# current_monitor_v1-1.net
KiCad netlist of a schematic drawn in EAGLE
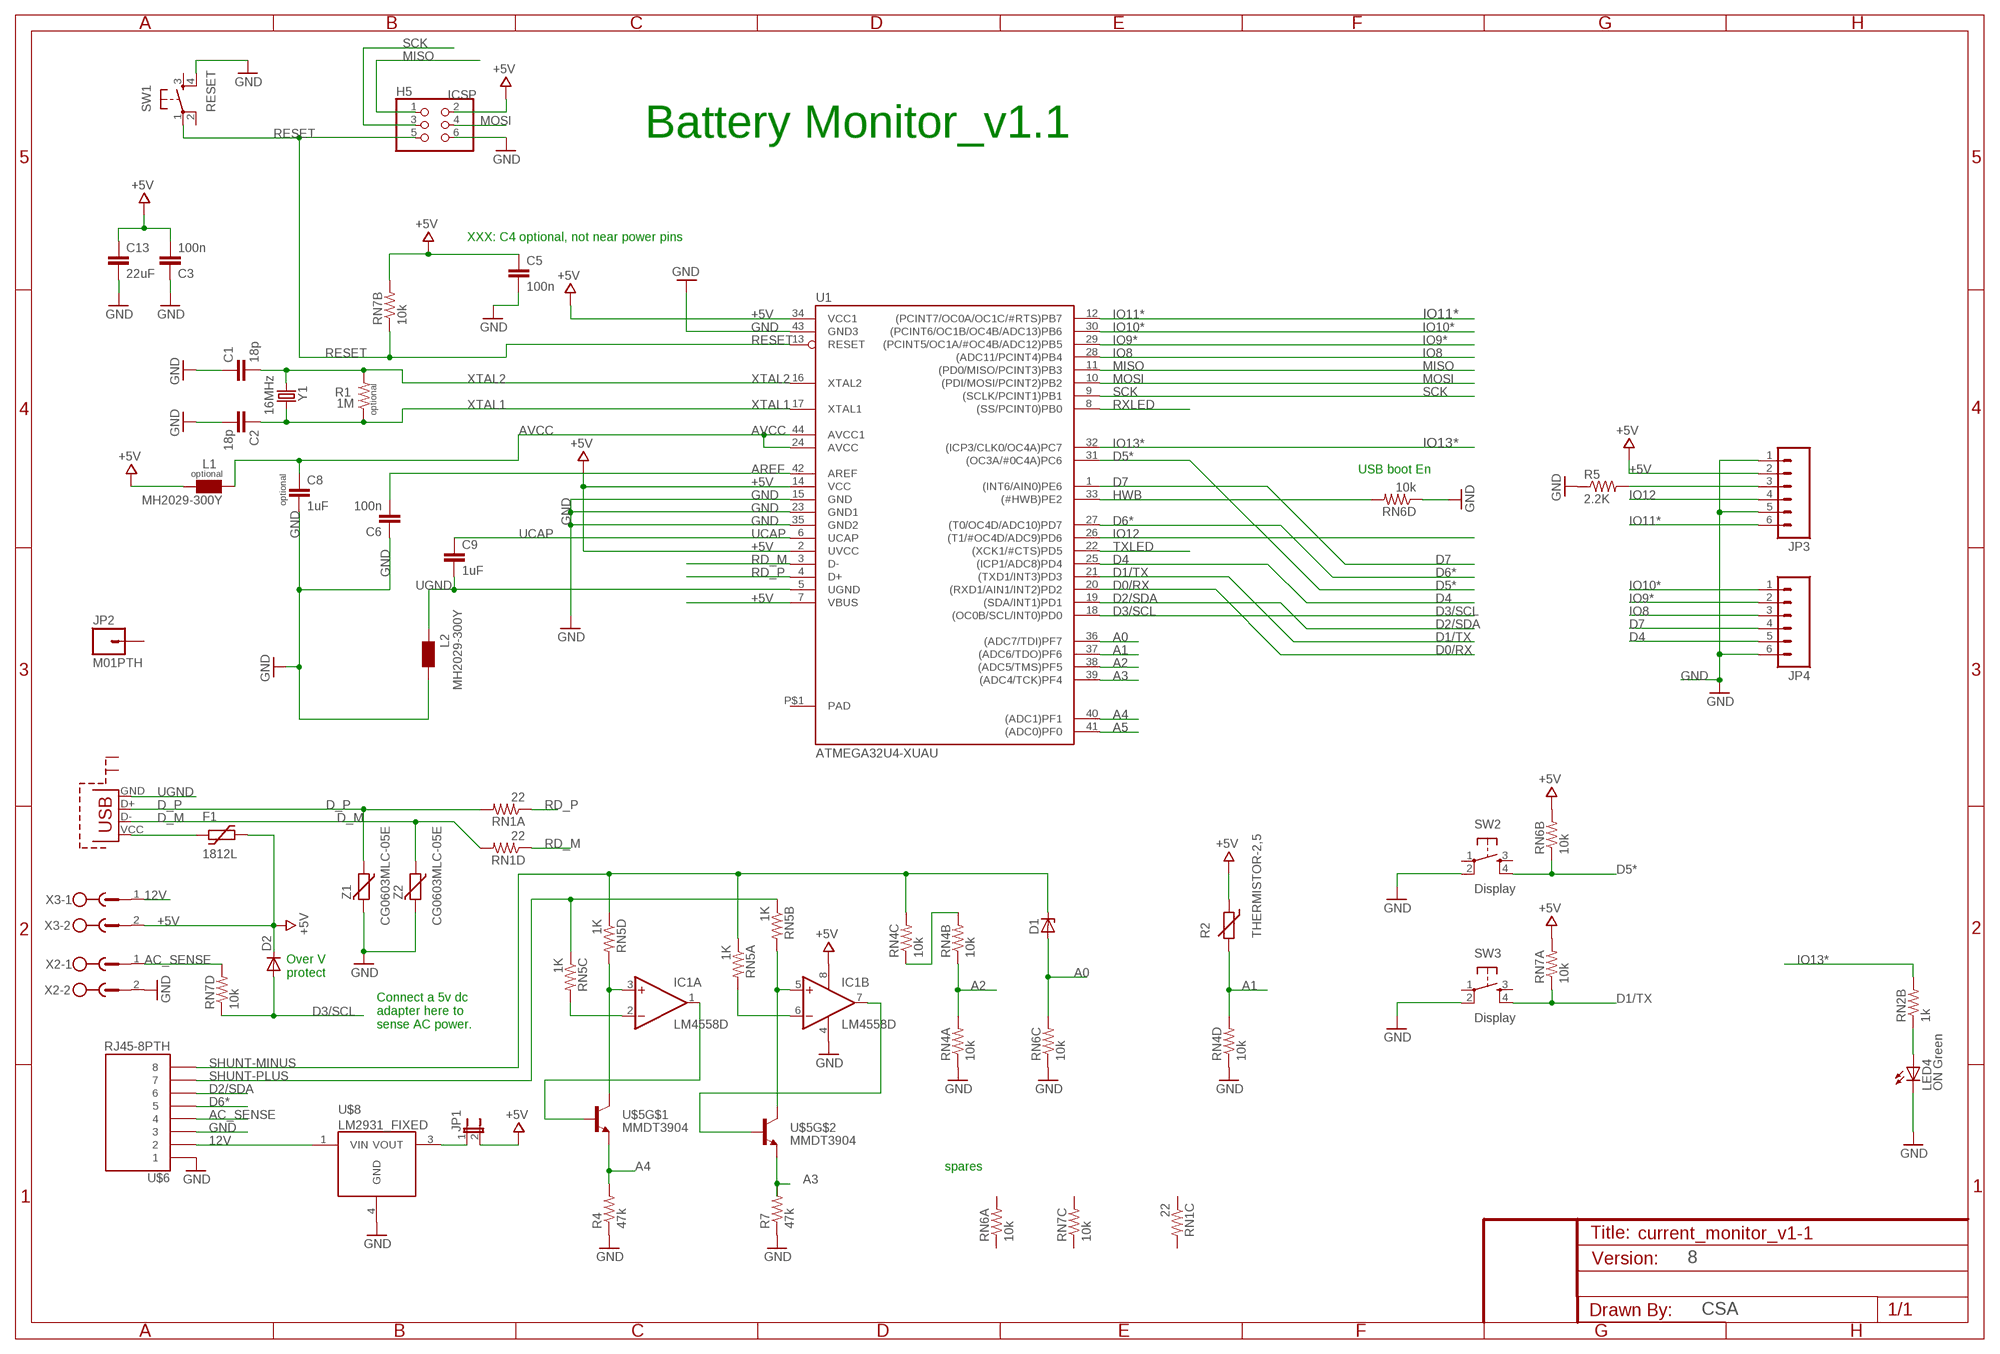
[diagram p0: schematic, sheet 1]

(export (version "E")
  (design (tool "Eeschema 10.0.6"))
  (components
    (comp (ref "C1")
      (value "18p")
      (footprint "eagle-import:0805")
      (libsource (lib "eagle-import") (part "CAP0805"))
    )
    (comp (ref "C2")
      (value "18p")
      (footprint "eagle-import:0805")
      (libsource (lib "eagle-import") (part "CAP0805"))
    )
    (comp (ref "C3")
      (value "100n")
      (footprint "eagle-import:0805")
      (libsource (lib "eagle-import") (part "CAP0805"))
    )
    (comp (ref "C5")
      (value "100n")
      (footprint "eagle-import:0805")
      (libsource (lib "eagle-import") (part "CAP0805"))
    )
    (comp (ref "C6")
      (value "100n")
      (footprint "eagle-import:0805")
      (libsource (lib "eagle-import") (part "CAP0805"))
    )
    (comp (ref "C8")
      (value "1uF")
      (footprint "eagle-import:0805")
      (libsource (lib "eagle-import") (part "CAP0805"))
    )
    (comp (ref "C9")
      (value "1uF")
      (footprint "eagle-import:0805")
      (libsource (lib "eagle-import") (part "CAP0805"))
    )
    (comp (ref "C13")
      (value "22uF")
      (footprint "eagle-import:1206")
      (libsource (lib "eagle-import") (part "CAP1206"))
    )
    (comp (ref "D1")
      (value "ZENER-DIODEZD-5")
      (footprint "eagle-import:ZDIO-5")
      (libsource (lib "eagle-import") (part "ZENER-DIODEZD-5"))
    )
    (comp (ref "D2")
      (value "DIODESMA")
      (footprint "eagle-import:SMA-DIODE")
      (libsource (lib "eagle-import") (part "DIODESMA"))
    )
    (comp (ref "F1")
      (value "1812L")
      (footprint "eagle-import:1812L")
      (libsource (lib "eagle-import") (part "1812L"))
    )
    (comp (ref "H5")
      (value "ICSP")
      (footprint "eagle-import:2X03")
      (libsource (lib "eagle-import") (part "PINHD-2X3"))
    )
    (comp (ref "IC1")
      (value "LM4558D")
      (footprint "eagle-import:SO08")
      (libsource (lib "eagle-import") (part "4558DLM"))
    )
    (comp (ref "JP1")
      (value "JUMPER-2-OLDPTH_LOCK")
      (footprint "eagle-import:1X02_LOCK")
      (libsource (lib "eagle-import") (part "JUMPER-2-OLDPTH_LOCK"))
    )
    (comp (ref "JP2")
      (value "M01PTH")
      (footprint "eagle-import:1X01")
      (libsource (lib "eagle-import") (part "M01PTH"))
    )
    (comp (ref "JP3")
      (value "M06FEMALE_LOCK")
      (footprint "eagle-import:1X06_FEMALE_LOCK.010")
      (libsource (lib "eagle-import") (part "M06FEMALE_LOCK"))
    )
    (comp (ref "JP4")
      (value "M06FEMALE_LOCK")
      (footprint "eagle-import:1X06_FEMALE_LOCK.010")
      (libsource (lib "eagle-import") (part "M06FEMALE_LOCK"))
    )
    (comp (ref "L1")
      (value "MH2029-300Y")
      (footprint "eagle-import:0805")
      (libsource (lib "eagle-import") (part "WE-CBF_0805"))
    )
    (comp (ref "L2")
      (value "MH2029-300Y")
      (footprint "eagle-import:0805")
      (libsource (lib "eagle-import") (part "WE-CBF_0805"))
    )
    (comp (ref "LED4")
      (value "ON Green")
      (footprint "eagle-import:LED0805")
      (libsource (lib "eagle-import") (part "LED0805"))
    )
    (comp (ref "R1")
      (value "1M")
      (footprint "eagle-import:0805")
      (libsource (lib "eagle-import") (part "RESISTOR0805-RES"))
    )
    (comp (ref "R2")
      (value "THERMISTOR-2,5")
      (footprint "eagle-import:RS-2,5")
      (libsource (lib "eagle-import") (part "THERMISTOR-2,5"))
    )
    (comp (ref "R4")
      (value "47k")
      (footprint "eagle-import:0805")
      (libsource (lib "eagle-import") (part "RESISTOR0805-RES"))
    )
    (comp (ref "R5")
      (value "2.2K")
      (footprint "eagle-import:0805")
      (libsource (lib "eagle-import") (part "RESISTOR0805-RES"))
    )
    (comp (ref "R7")
      (value "47k")
      (footprint "eagle-import:0805")
      (libsource (lib "eagle-import") (part "RESISTOR0805-RES"))
    )
    (comp (ref "RN1")
      (value "22")
      (footprint "eagle-import:CRA06S")
      (libsource (lib "eagle-import") (part "RESISTOR-ARRAYCRA06S"))
    )
    (comp (ref "RN2")
      (value "1k")
      (footprint "eagle-import:CRA06S")
      (libsource (lib "eagle-import") (part "RESISTOR-ARRAYCRA06S"))
    )
    (comp (ref "RN4")
      (value "10k")
      (footprint "eagle-import:CRA06S")
      (libsource (lib "eagle-import") (part "RESISTOR-ARRAYCRA06S"))
    )
    (comp (ref "RN5")
      (value "1K")
      (footprint "eagle-import:CRA06S")
      (libsource (lib "eagle-import") (part "RESISTOR-ARRAYCRA06S"))
    )
    (comp (ref "RN6")
      (value "10k")
      (footprint "eagle-import:CRA06S")
      (libsource (lib "eagle-import") (part "RESISTOR-ARRAYCRA06S"))
    )
    (comp (ref "RN7")
      (value "10k")
      (footprint "eagle-import:CRA06S")
      (libsource (lib "eagle-import") (part "RESISTOR-ARRAYCRA06S"))
    )
    (comp (ref "SW1")
      (value "RESET")
      (footprint "eagle-import:TACTILE-PTH")
      (libsource (lib "eagle-import") (part "TAC_SWITCHPTH"))
    )
    (comp (ref "SW2")
      (value "Display")
      (footprint "eagle-import:TACTILE-PTH")
      (libsource (lib "eagle-import") (part "TAC_SWITCHPTH"))
    )
    (comp (ref "SW3")
      (value "Display")
      (footprint "eagle-import:TACTILE-PTH")
      (libsource (lib "eagle-import") (part "TAC_SWITCHPTH"))
    )
    (comp (ref "U$5")
      (value "MMDT3904")
      (footprint "eagle-import:SOT363")
      (libsource (lib "eagle-import") (part "MMDT3904"))
    )
    (comp (ref "U$6")
      (value "RJ45-8PTH")
      (footprint "eagle-import:RJ45-8")
      (libsource (lib "eagle-import") (part "RJ45-8PTH"))
    )
    (comp (ref "U$8")
      (value "LM2931_FIXED")
      (footprint "eagle-import:DPAK")
      (libsource (lib "eagle-import") (part "LM2931_FIXED"))
    )
    (comp (ref "U$12")
      (value "USB-MICRO-B-UNIVERSAL")
      (footprint "eagle-import:USB-MICRO-B-UNIVERSAL")
      (libsource (lib "eagle-import") (part "USB-MICRO-B-UNIVERSAL"))
    )
    (comp (ref "U1")
      (value "ATMEGA32U4-XUAU")
      (footprint "eagle-import:TQFP44-PAD")
      (libsource (lib "eagle-import") (part "ATMEGA32U4-XUAU"))
    )
    (comp (ref "X2")
      (value "MSTBV2")
      (footprint "eagle-import:MSTBV2")
      (libsource (lib "eagle-import") (part "MSTBV2"))
    )
    (comp (ref "X3")
      (value "MSTBV2")
      (footprint "eagle-import:MSTBV2")
      (libsource (lib "eagle-import") (part "MSTBV2"))
    )
    (comp (ref "Y1")
      (value "16MHz")
      (footprint "eagle-import:HC49US")
      (libsource (lib "eagle-import") (part "CRYSTALHC49US"))
    )
    (comp (ref "Z1")
      (value "CG0603MLC-05E")
      (footprint "eagle-import:CT_CN0603")
      (libsource (lib "eagle-import") (part "VARISTORCN0603"))
    )
    (comp (ref "Z2")
      (value "CG0603MLC-05E")
      (footprint "eagle-import:CT_CN0603")
      (libsource (lib "eagle-import") (part "VARISTORCN0603"))
    )
  )
  (nets
    (net (code "1") (name "+5V") (class "Default")
      (node (ref "C13") (pin "1") (pinfunction "1_1") (pintype "passive"))
      (node (ref "C3") (pin "2") (pinfunction "2_2") (pintype "passive"))
      (node (ref "C5") (pin "1") (pinfunction "1_1") (pintype "passive"))
      (node (ref "D2") (pin "C") (pinfunction "C_C") (pintype "passive"))
      (node (ref "F1") (pin "P$2") (pinfunction "2_P$2") (pintype "passive"))
      (node (ref "H5") (pin "2") (pinfunction "2_2") (pintype "passive"))
      (node (ref "IC1") (pin "8") (pinfunction "V+_8") (pintype "power_in"))
      (node (ref "JP1") (pin "2") (pinfunction "2_2") (pintype "passive"))
      (node (ref "JP3") (pin "2") (pinfunction "2_2") (pintype "passive"))
      (node (ref "L1") (pin "1") (pinfunction "1_1") (pintype "passive"))
      (node (ref "R2") (pin "1") (pinfunction "1_1") (pintype "passive"))
      (node (ref "RN6") (pin "7") (pinfunction "2_7") (pintype "passive"))
      (node (ref "RN7") (pin "7") (pinfunction "2_7") (pintype "passive"))
      (node (ref "RN7") (pin "8") (pinfunction "2_8") (pintype "passive"))
      (node (ref "U1") (pin "14") (pinfunction "VCC_14") (pintype "power_in"))
      (node (ref "U1") (pin "2") (pinfunction "UVCC_2") (pintype "power_in"))
      (node (ref "U1") (pin "34") (pinfunction "VCC1_34") (pintype "power_in"))
      (node (ref "U1") (pin "7") (pinfunction "VBUS_7") (pintype "input"))
      (node (ref "X3") (pin "2") (pinfunction "SK_2") (pintype "passive"))
    )
    (net (code "2") (name "/12V") (class "Default")
      (node (ref "U$6") (pin "2") (pinfunction "2_2") (pintype "bidirectional"))
      (node (ref "U$8") (pin "1") (pinfunction "VIN_1") (pintype "bidirectional"))
      (node (ref "X3") (pin "1") (pinfunction "SK_1") (pintype "passive"))
    )
    (net (code "3") (name "/A0") (class "Default")
      (node (ref "D1") (pin "A") (pinfunction "A_A") (pintype "passive"))
      (node (ref "RN6") (pin "6") (pinfunction "2_6") (pintype "passive"))
      (node (ref "U1") (pin "36") (pinfunction "(ADC7/TDI)PF7_36") (pintype "bidirectional"))
    )
    (net (code "4") (name "/A1") (class "Default")
      (node (ref "R2") (pin "2") (pinfunction "2_2") (pintype "passive"))
      (node (ref "RN4") (pin "5") (pinfunction "2_5") (pintype "passive"))
      (node (ref "U1") (pin "37") (pinfunction "(ADC6/TDO)PF6_37") (pintype "bidirectional"))
    )
    (net (code "5") (name "/A2") (class "Default")
      (node (ref "RN4") (pin "2") (pinfunction "1_2") (pintype "passive"))
      (node (ref "RN4") (pin "8") (pinfunction "2_8") (pintype "passive"))
      (node (ref "U1") (pin "38") (pinfunction "(ADC5/TMS)PF5_38") (pintype "bidirectional"))
    )
    (net (code "6") (name "/A3") (class "Default")
      (node (ref "R7") (pin "2") (pinfunction "2_2") (pintype "passive"))
      (node (ref "U$5") (pin "1") (pinfunction "E_1") (pintype "passive"))
      (node (ref "U1") (pin "39") (pinfunction "(ADC4/TCK)PF4_39") (pintype "bidirectional"))
    )
    (net (code "7") (name "/A4") (class "Default")
      (node (ref "R4") (pin "2") (pinfunction "2_2") (pintype "passive"))
      (node (ref "U$5") (pin "4") (pinfunction "E_4") (pintype "passive"))
      (node (ref "U1") (pin "40") (pinfunction "(ADC1)PF1_40") (pintype "bidirectional"))
    )
    (net (code "8") (name "/A5") (class "Default")
      (node (ref "U1") (pin "41") (pinfunction "(ADC0)PF0_41") (pintype "bidirectional"))
    )
    (net (code "9") (name "/AC_SENSE") (class "Default")
      (node (ref "RN7") (pin "5") (pinfunction "2_5") (pintype "passive"))
      (node (ref "U$6") (pin "4") (pinfunction "4_4") (pintype "bidirectional"))
      (node (ref "X2") (pin "1") (pinfunction "SK_1") (pintype "passive"))
    )
    (net (code "10") (name "/AREF") (class "Default")
      (node (ref "C6") (pin "2") (pinfunction "2_2") (pintype "passive"))
      (node (ref "U1") (pin "42") (pinfunction "AREF_42") (pintype "power_in"))
    )
    (net (code "11") (name "/AVCC") (class "Default")
      (node (ref "C8") (pin "1") (pinfunction "1_1") (pintype "passive"))
      (node (ref "L1") (pin "2") (pinfunction "2_2") (pintype "passive"))
      (node (ref "U1") (pin "24") (pinfunction "AVCC_24") (pintype "power_in"))
      (node (ref "U1") (pin "44") (pinfunction "AVCC1_44") (pintype "power_in"))
    )
    (net (code "12") (name "/D0{slash}RX") (class "Default")
      (node (ref "U1") (pin "20") (pinfunction "(RXD1/AIN1/INT2)PD2_20") (pintype "bidirectional"))
    )
    (net (code "13") (name "/D1{slash}TX") (class "Default")
      (node (ref "RN7") (pin "1") (pinfunction "1_1") (pintype "passive"))
      (node (ref "SW3") (pin "4") (pinfunction "4_4") (pintype "passive"))
      (node (ref "U1") (pin "21") (pinfunction "(TXD1/INT3)PD3_21") (pintype "bidirectional"))
    )
    (net (code "14") (name "/D2{slash}SDA") (class "Default")
      (node (ref "U$6") (pin "6") (pinfunction "6_6") (pintype "bidirectional"))
      (node (ref "U1") (pin "19") (pinfunction "(SDA/INT1)PD1_19") (pintype "bidirectional"))
    )
    (net (code "15") (name "/D3{slash}SCL") (class "Default")
      (node (ref "D2") (pin "A") (pinfunction "A_A") (pintype "passive"))
      (node (ref "RN7") (pin "4") (pinfunction "1_4") (pintype "passive"))
      (node (ref "U1") (pin "18") (pinfunction "(OC0B/SCL/INT0)PD0_18") (pintype "bidirectional"))
    )
    (net (code "16") (name "/D4") (class "Default")
      (node (ref "JP4") (pin "5") (pinfunction "5_5") (pintype "passive"))
      (node (ref "U1") (pin "25") (pinfunction "(ICP1/ADC8)PD4_25") (pintype "bidirectional"))
    )
    (net (code "17") (name "/D5*") (class "Default")
      (node (ref "RN6") (pin "2") (pinfunction "1_2") (pintype "passive"))
      (node (ref "SW2") (pin "4") (pinfunction "4_4") (pintype "passive"))
      (node (ref "U1") (pin "31") (pinfunction "(OC3A/#0C4A)PC6_31") (pintype "bidirectional"))
    )
    (net (code "18") (name "/D6*") (class "Default")
      (node (ref "U$6") (pin "5") (pinfunction "5_5") (pintype "bidirectional"))
      (node (ref "U1") (pin "27") (pinfunction "(T0/OC4D/ADC10)PD7_27") (pintype "bidirectional"))
    )
    (net (code "19") (name "/D7") (class "Default")
      (node (ref "JP4") (pin "4") (pinfunction "4_4") (pintype "passive"))
      (node (ref "U1") (pin "1") (pinfunction "(INT6/AIN0)PE6_1") (pintype "bidirectional"))
    )
    (net (code "20") (name "/D_M") (class "Default")
      (node (ref "RN1") (pin "5") (pinfunction "2_5") (pintype "passive"))
      (node (ref "U$12") (pin "D-") (pinfunction "D-_D-") (pintype "bidirectional"))
      (node (ref "Z2") (pin "1") (pinfunction "1_1") (pintype "passive"))
    )
    (net (code "21") (name "/D_P") (class "Default")
      (node (ref "RN1") (pin "8") (pinfunction "2_8") (pintype "passive"))
      (node (ref "U$12") (pin "D+") (pinfunction "D+_D+") (pintype "bidirectional"))
      (node (ref "Z1") (pin "1") (pinfunction "1_1") (pintype "passive"))
    )
    (net (code "22") (name "/HWB") (class "Default")
      (node (ref "RN6") (pin "5") (pinfunction "2_5") (pintype "passive"))
      (node (ref "U1") (pin "33") (pinfunction "(#HWB)PE2_33") (pintype "bidirectional"))
    )
    (net (code "23") (name "/IO8") (class "Default")
      (node (ref "JP4") (pin "3") (pinfunction "3_3") (pintype "passive"))
      (node (ref "U1") (pin "28") (pinfunction "(ADC11/PCINT4)PB4_28") (pintype "bidirectional"))
    )
    (net (code "24") (name "/IO9*") (class "Default")
      (node (ref "JP4") (pin "2") (pinfunction "2_2") (pintype "passive"))
      (node (ref "U1") (pin "29") (pinfunction "(PCINT5/OC1A/#OC4B/ADC12)PB5_29") (pintype "bidirectional"))
    )
    (net (code "25") (name "/IO10*") (class "Default")
      (node (ref "JP4") (pin "1") (pinfunction "1_1") (pintype "passive"))
      (node (ref "U1") (pin "30") (pinfunction "(PCINT6/OC1B/OC4B/ADC13)PB6_30") (pintype "bidirectional"))
    )
    (net (code "26") (name "/IO11*") (class "Default")
      (node (ref "JP3") (pin "6") (pinfunction "6_6") (pintype "passive"))
      (node (ref "U1") (pin "12") (pinfunction "(PCINT7/OC0A/OC1C/#RTS)PB7_12") (pintype "bidirectional"))
    )
    (net (code "27") (name "/IO12") (class "Default")
      (node (ref "JP3") (pin "4") (pinfunction "4_4") (pintype "passive"))
      (node (ref "U1") (pin "26") (pinfunction "(T1/#OC4D/ADC9)PD6_26") (pintype "bidirectional"))
    )
    (net (code "28") (name "/IO13*") (class "Default")
      (node (ref "RN2") (pin "7") (pinfunction "2_7") (pintype "passive"))
      (node (ref "U1") (pin "32") (pinfunction "(ICP3/CLK0/OC4A)PC7_32") (pintype "bidirectional"))
    )
    (net (code "29") (name "/MISO") (class "Default")
      (node (ref "H5") (pin "1") (pinfunction "1_1") (pintype "passive"))
      (node (ref "U1") (pin "11") (pinfunction "(PD0/MISO/PCINT3)PB3_11") (pintype "bidirectional"))
    )
    (net (code "30") (name "/MOSI") (class "Default")
      (node (ref "H5") (pin "4") (pinfunction "4_4") (pintype "passive"))
      (node (ref "U1") (pin "10") (pinfunction "(PDI/MOSI/PCINT2)PB2_10") (pintype "bidirectional"))
    )
    (net (code "31") (name "/PAD") (class "Default")
      (node (ref "U1") (pin "P$1") (pinfunction "PAD_P$1") (pintype "power_in"))
    )
    (net (code "32") (name "/RD_M") (class "Default")
      (node (ref "RN1") (pin "4") (pinfunction "1_4") (pintype "passive"))
      (node (ref "U1") (pin "3") (pinfunction "D-_3") (pintype "bidirectional"))
    )
    (net (code "33") (name "/RD_P") (class "Default")
      (node (ref "RN1") (pin "1") (pinfunction "1_1") (pintype "passive"))
      (node (ref "U1") (pin "4") (pinfunction "D+_4") (pintype "bidirectional"))
    )
    (net (code "34") (name "/RESET") (class "Default")
      (node (ref "H5") (pin "5") (pinfunction "5_5") (pintype "passive"))
      (node (ref "RN7") (pin "2") (pinfunction "1_2") (pintype "passive"))
      (node (ref "SW1") (pin "1") (pinfunction "1_1") (pintype "passive"))
      (node (ref "U1") (pin "13") (pinfunction "RESET_13") (pintype "input"))
    )
    (net (code "35") (name "/RXLED") (class "Default")
      (node (ref "U1") (pin "8") (pinfunction "(SS/PCINT0)PB0_8") (pintype "bidirectional"))
    )
    (net (code "36") (name "/SCK") (class "Default")
      (node (ref "H5") (pin "3") (pinfunction "3_3") (pintype "passive"))
      (node (ref "U1") (pin "9") (pinfunction "(SCLK/PCINT1)PB1_9") (pintype "bidirectional"))
    )
    (net (code "37") (name "/SHUNT-MINUS") (class "Default")
      (node (ref "D1") (pin "C") (pinfunction "C_C") (pintype "passive"))
      (node (ref "RN4") (pin "6") (pinfunction "2_6") (pintype "passive"))
      (node (ref "RN5") (pin "1") (pinfunction "1_1") (pintype "passive"))
      (node (ref "RN5") (pin "4") (pinfunction "1_4") (pintype "passive"))
      (node (ref "U$6") (pin "8") (pinfunction "8_8") (pintype "bidirectional"))
    )
    (net (code "38") (name "/SHUNT-PLUS") (class "Default")
      (node (ref "RN5") (pin "2") (pinfunction "1_2") (pintype "passive"))
      (node (ref "RN5") (pin "3") (pinfunction "1_3") (pintype "passive"))
      (node (ref "U$6") (pin "7") (pinfunction "7_7") (pintype "bidirectional"))
    )
    (net (code "39") (name "/TXLED") (class "Default")
      (node (ref "U1") (pin "22") (pinfunction "(XCK1/#CTS)PD5_22") (pintype "bidirectional"))
    )
    (net (code "40") (name "/UCAP") (class "Default")
      (node (ref "C9") (pin "1") (pinfunction "1_1") (pintype "passive"))
      (node (ref "U1") (pin "6") (pinfunction "UCAP_6") (pintype "passive"))
    )
    (net (code "41") (name "/UGND") (class "Default")
      (node (ref "C9") (pin "2") (pinfunction "2_2") (pintype "passive"))
      (node (ref "L2") (pin "1") (pinfunction "1_1") (pintype "passive"))
      (node (ref "U$12") (pin "GND") (pinfunction "GND_GND") (pintype "bidirectional"))
      (node (ref "U1") (pin "5") (pinfunction "UGND_5") (pintype "power_in"))
    )
    (net (code "42") (name "/XTAL1") (class "Default")
      (node (ref "C2") (pin "1") (pinfunction "1_1") (pintype "passive"))
      (node (ref "R1") (pin "1") (pinfunction "1_1") (pintype "passive"))
      (node (ref "U1") (pin "17") (pinfunction "XTAL1_17") (pintype "bidirectional"))
      (node (ref "Y1") (pin "2") (pinfunction "2_2") (pintype "passive"))
    )
    (net (code "43") (name "/XTAL2") (class "Default")
      (node (ref "C1") (pin "2") (pinfunction "2_2") (pintype "passive"))
      (node (ref "R1") (pin "2") (pinfunction "2_2") (pintype "passive"))
      (node (ref "U1") (pin "16") (pinfunction "XTAL2_16") (pintype "bidirectional"))
      (node (ref "Y1") (pin "1") (pinfunction "1_1") (pintype "passive"))
    )
    (net (code "44") (name "GND") (class "Default")
      (node (ref "C1") (pin "1") (pinfunction "1_1") (pintype "passive"))
      (node (ref "C13") (pin "2") (pinfunction "2_2") (pintype "passive"))
      (node (ref "C2") (pin "2") (pinfunction "2_2") (pintype "passive"))
      (node (ref "C3") (pin "1") (pinfunction "1_1") (pintype "passive"))
      (node (ref "C5") (pin "2") (pinfunction "2_2") (pintype "passive"))
      (node (ref "C6") (pin "1") (pinfunction "1_1") (pintype "passive"))
      (node (ref "C8") (pin "2") (pinfunction "2_2") (pintype "passive"))
      (node (ref "H5") (pin "6") (pinfunction "6_6") (pintype "passive"))
      (node (ref "IC1") (pin "4") (pinfunction "V-_4") (pintype "power_in"))
      (node (ref "JP3") (pin "1") (pinfunction "1_1") (pintype "passive"))
      (node (ref "JP3") (pin "5") (pinfunction "5_5") (pintype "passive"))
      (node (ref "JP4") (pin "6") (pinfunction "6_6") (pintype "passive"))
      (node (ref "L2") (pin "2") (pinfunction "2_2") (pintype "passive"))
      (node (ref "LED4") (pin "C") (pinfunction "C_C") (pintype "passive"))
      (node (ref "R4") (pin "1") (pinfunction "1_1") (pintype "passive"))
      (node (ref "R5") (pin "1") (pinfunction "1_1") (pintype "passive"))
      (node (ref "R7") (pin "1") (pinfunction "1_1") (pintype "passive"))
      (node (ref "RN4") (pin "1") (pinfunction "1_1") (pintype "passive"))
      (node (ref "RN4") (pin "4") (pinfunction "1_4") (pintype "passive"))
      (node (ref "RN6") (pin "3") (pinfunction "1_3") (pintype "passive"))
      (node (ref "RN6") (pin "4") (pinfunction "1_4") (pintype "passive"))
      (node (ref "SW1") (pin "4") (pinfunction "4_4") (pintype "passive"))
      (node (ref "SW2") (pin "2") (pinfunction "2_2") (pintype "passive"))
      (node (ref "SW3") (pin "2") (pinfunction "2_2") (pintype "passive"))
      (node (ref "U$6") (pin "1") (pinfunction "1_1") (pintype "bidirectional"))
      (node (ref "U$6") (pin "3") (pinfunction "3_3") (pintype "bidirectional"))
      (node (ref "U$8") (pin "4") (pinfunction "GND_4") (pintype "bidirectional"))
      (node (ref "U1") (pin "15") (pinfunction "GND_15") (pintype "power_in"))
      (node (ref "U1") (pin "23") (pinfunction "GND1_23") (pintype "power_in"))
      (node (ref "U1") (pin "35") (pinfunction "GND2_35") (pintype "power_in"))
      (node (ref "U1") (pin "43") (pinfunction "GND3_43") (pintype "power_in"))
      (node (ref "X2") (pin "2") (pinfunction "SK_2") (pintype "passive"))
      (node (ref "Z1") (pin "2") (pinfunction "2_2") (pintype "passive"))
      (node (ref "Z2") (pin "2") (pinfunction "2_2") (pintype "passive"))
    )
    (net (code "45") (name "Net-(F1-1)") (class "Default")
      (node (ref "F1") (pin "P$1") (pinfunction "1_P$1") (pintype "passive"))
      (node (ref "U$12") (pin "VCC") (pinfunction "VBUS_VCC") (pintype "bidirectional"))
    )
    (net (code "46") (name "Net-(IC1A-+IN)") (class "Default")
      (node (ref "IC1") (pin "3") (pinfunction "+IN_3") (pintype "input"))
      (node (ref "RN5") (pin "5") (pinfunction "2_5") (pintype "passive"))
      (node (ref "U$5") (pin "3") (pinfunction "C_3") (pintype "passive"))
    )
    (net (code "47") (name "Net-(IC1A--IN)") (class "Default")
      (node (ref "IC1") (pin "2") (pinfunction "-IN_2") (pintype "input"))
      (node (ref "RN5") (pin "6") (pinfunction "2_6") (pintype "passive"))
    )
    (net (code "48") (name "Net-(IC1A-OUT)") (class "Default")
      (node (ref "IC1") (pin "1") (pinfunction "OUT_1") (pintype "output"))
      (node (ref "U$5") (pin "5") (pinfunction "B_5") (pintype "passive"))
    )
    (net (code "49") (name "Net-(IC1B-+IN)") (class "Default")
      (node (ref "IC1") (pin "5") (pinfunction "+IN_5") (pintype "input"))
      (node (ref "RN5") (pin "7") (pinfunction "2_7") (pintype "passive"))
      (node (ref "U$5") (pin "6") (pinfunction "C_6") (pintype "passive"))
    )
    (net (code "50") (name "Net-(IC1B--IN)") (class "Default")
      (node (ref "IC1") (pin "6") (pinfunction "-IN_6") (pintype "input"))
      (node (ref "RN5") (pin "8") (pinfunction "2_8") (pintype "passive"))
    )
    (net (code "51") (name "Net-(IC1B-OUT)") (class "Default")
      (node (ref "IC1") (pin "7") (pinfunction "OUT_7") (pintype "output"))
      (node (ref "U$5") (pin "2") (pinfunction "B_2") (pintype "passive"))
    )
    (net (code "52") (name "Net-(JP3-Pad3)") (class "Default")
      (node (ref "JP3") (pin "3") (pinfunction "3_3") (pintype "passive"))
      (node (ref "R5") (pin "2") (pinfunction "2_2") (pintype "passive"))
    )
    (net (code "53") (name "Net-(RN2B-1)") (class "Default")
      (node (ref "LED4") (pin "A") (pinfunction "A_A") (pintype "passive"))
      (node (ref "RN2") (pin "2") (pinfunction "1_2") (pintype "passive"))
    )
    (net (code "54") (name "Net-(RN4B-2)") (class "Default")
      (node (ref "RN4") (pin "3") (pinfunction "1_3") (pintype "passive"))
      (node (ref "RN4") (pin "7") (pinfunction "2_7") (pintype "passive"))
    )
    (net (code "55") (name "Net-(U$8-VOUT)") (class "Default")
      (node (ref "JP1") (pin "1") (pinfunction "1_1") (pintype "passive"))
      (node (ref "U$8") (pin "3") (pinfunction "VOUT_3") (pintype "bidirectional"))
    )
    (net (code "56") (name "unconnected-(JP2-Pad1)") (class "Default")
      (node (ref "JP2") (pin "1") (pinfunction "1_1") (pintype "passive"))
    )
    (net (code "57") (name "unconnected-(RN1C-1-Pad3)") (class "Default")
      (node (ref "RN1") (pin "3") (pinfunction "1_3") (pintype "passive"))
    )
    (net (code "58") (name "unconnected-(RN1C-2-Pad6)") (class "Default")
      (node (ref "RN1") (pin "6") (pinfunction "2_6") (pintype "passive"))
    )
    (net (code "59") (name "unconnected-(RN6-Pad1)") (class "Default")
      (node (ref "RN6") (pin "1") (pinfunction "1_1") (pintype "passive"))
    )
    (net (code "60") (name "unconnected-(RN6A-2-Pad8)") (class "Default")
      (node (ref "RN6") (pin "8") (pinfunction "2_8") (pintype "passive"))
    )
    (net (code "61") (name "unconnected-(RN7C-1-Pad3)") (class "Default")
      (node (ref "RN7") (pin "3") (pinfunction "1_3") (pintype "passive"))
    )
    (net (code "62") (name "unconnected-(RN7C-2-Pad6)") (class "Default")
      (node (ref "RN7") (pin "6") (pinfunction "2_6") (pintype "passive"))
    )
    (net (code "63") (name "unconnected-(SW1-Pad2)") (class "Default")
      (node (ref "SW1") (pin "2") (pinfunction "2_2") (pintype "passive"))
    )
    (net (code "64") (name "unconnected-(SW1-Pad3)") (class "Default")
      (node (ref "SW1") (pin "3") (pinfunction "3_3") (pintype "passive"))
    )
    (net (code "65") (name "unconnected-(SW2-Pad1)") (class "Default")
      (node (ref "SW2") (pin "1") (pinfunction "1_1") (pintype "passive"))
    )
    (net (code "66") (name "unconnected-(SW2-Pad3)") (class "Default")
      (node (ref "SW2") (pin "3") (pinfunction "3_3") (pintype "passive"))
    )
    (net (code "67") (name "unconnected-(SW3-Pad1)") (class "Default")
      (node (ref "SW3") (pin "1") (pinfunction "1_1") (pintype "passive"))
    )
    (net (code "68") (name "unconnected-(SW3-Pad3)") (class "Default")
      (node (ref "SW3") (pin "3") (pinfunction "3_3") (pintype "passive"))
    )
    (net (code "69") (name "unconnected-(U$12-SHIELD1-PadP$7)") (class "Default")
      (node (ref "U$12") (pin "P$7") (pinfunction "SHIELD1_P$7") (pintype "bidirectional"))
    )
    (net (code "70") (name "unconnected-(U$12-SHIELD2-PadP$8)") (class "Default")
      (node (ref "U$12") (pin "P$8") (pinfunction "SHIELD2_P$8") (pintype "bidirectional"))
    )
  )
)
